# rev_1_3.net
KiCad netlist of a schematic drawn in EAGLE
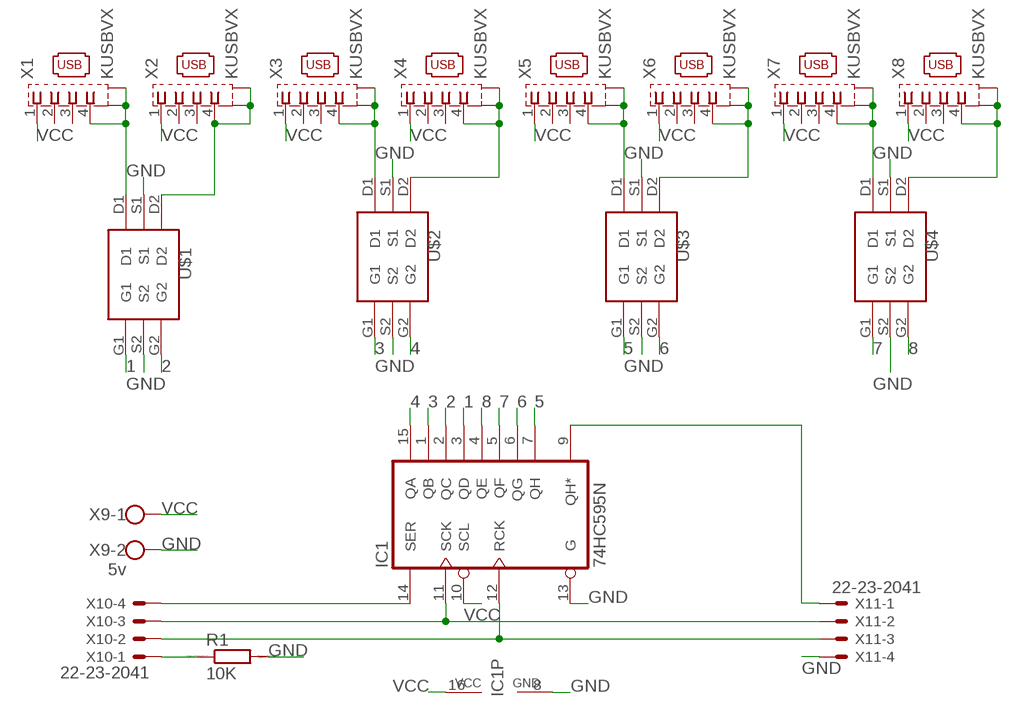
[diagram p0: schematic, sheet 1]

(export (version "E")
  (design (tool "Eeschema 10.0.6"))
  (components
    (comp (ref "IC1")
      (value "74HC595N")
      (footprint "eagle-import:DIL16")
      (libsource (lib "eagle-import") (part "74595NHC"))
    )
    (comp (ref "R1")
      (value "10K")
      (footprint "eagle-import:0204_7")
      (libsource (lib "eagle-import") (part "R0204/7"))
    )
    (comp (ref "U$1")
      (value "FDC6305N")
      (footprint "eagle-import:FDC6305")
      (libsource (lib "eagle-import") (part "FDC6305N"))
    )
    (comp (ref "U$2")
      (value "FDC6305N")
      (footprint "eagle-import:FDC6305")
      (libsource (lib "eagle-import") (part "FDC6305N"))
    )
    (comp (ref "U$3")
      (value "FDC6305N")
      (footprint "eagle-import:FDC6305")
      (libsource (lib "eagle-import") (part "FDC6305N"))
    )
    (comp (ref "U$4")
      (value "FDC6305N")
      (footprint "eagle-import:FDC6305")
      (libsource (lib "eagle-import") (part "FDC6305N"))
    )
    (comp (ref "X1")
      (value "KUSBVX")
      (footprint "eagle-import:KUSBVX")
      (libsource (lib "eagle-import") (part "KUSBVX"))
    )
    (comp (ref "X2")
      (value "KUSBVX")
      (footprint "eagle-import:KUSBVX")
      (libsource (lib "eagle-import") (part "KUSBVX"))
    )
    (comp (ref "X3")
      (value "KUSBVX")
      (footprint "eagle-import:KUSBVX")
      (libsource (lib "eagle-import") (part "KUSBVX"))
    )
    (comp (ref "X4")
      (value "KUSBVX")
      (footprint "eagle-import:KUSBVX")
      (libsource (lib "eagle-import") (part "KUSBVX"))
    )
    (comp (ref "X5")
      (value "KUSBVX")
      (footprint "eagle-import:KUSBVX")
      (libsource (lib "eagle-import") (part "KUSBVX"))
    )
    (comp (ref "X6")
      (value "KUSBVX")
      (footprint "eagle-import:KUSBVX")
      (libsource (lib "eagle-import") (part "KUSBVX"))
    )
    (comp (ref "X7")
      (value "KUSBVX")
      (footprint "eagle-import:KUSBVX")
      (libsource (lib "eagle-import") (part "KUSBVX"))
    )
    (comp (ref "X8")
      (value "KUSBVX")
      (footprint "eagle-import:KUSBVX")
      (libsource (lib "eagle-import") (part "KUSBVX"))
    )
    (comp (ref "X9")
      (value "5v")
      (footprint "eagle-import:W237-102")
      (fields (field (name "MPN") "237-102"))
      (libsource (lib "eagle-import") (part "W237-102"))
    )
    (comp (ref "X10")
      (value "22-23-2041")
      (footprint "eagle-import:22-23-2041")
      (fields (field (name "MF") "MOLEX"))
      (libsource (lib "eagle-import") (part "22-23-2041"))
    )
    (comp (ref "X11")
      (value "22-23-2041")
      (footprint "eagle-import:22-23-2041")
      (fields (field (name "MF") "MOLEX"))
      (libsource (lib "eagle-import") (part "22-23-2041"))
    )
  )
  (nets
    (net (code "1") (name "/1") (class "Default")
      (node (ref "IC1") (pin "3") (pinfunction "QD_3") (pintype "tri_state"))
      (node (ref "U$1") (pin "G1") (pinfunction "G1_G1") (pintype "bidirectional"))
    )
    (net (code "2") (name "/2") (class "Default")
      (node (ref "IC1") (pin "2") (pinfunction "QC_2") (pintype "tri_state"))
      (node (ref "U$1") (pin "G2") (pinfunction "G2_G2") (pintype "bidirectional"))
    )
    (net (code "3") (name "/3") (class "Default")
      (node (ref "IC1") (pin "1") (pinfunction "QB_1") (pintype "tri_state"))
      (node (ref "U$2") (pin "G1") (pinfunction "G1_G1") (pintype "bidirectional"))
    )
    (net (code "4") (name "/4") (class "Default")
      (node (ref "IC1") (pin "15") (pinfunction "QA_15") (pintype "tri_state"))
      (node (ref "U$2") (pin "G2") (pinfunction "G2_G2") (pintype "bidirectional"))
    )
    (net (code "5") (name "/5") (class "Default")
      (node (ref "IC1") (pin "7") (pinfunction "QH_7") (pintype "tri_state"))
      (node (ref "U$3") (pin "G1") (pinfunction "G1_G1") (pintype "bidirectional"))
    )
    (net (code "6") (name "/6") (class "Default")
      (node (ref "IC1") (pin "6") (pinfunction "QG_6") (pintype "tri_state"))
      (node (ref "U$3") (pin "G2") (pinfunction "G2_G2") (pintype "bidirectional"))
    )
    (net (code "7") (name "/7") (class "Default")
      (node (ref "IC1") (pin "5") (pinfunction "QF_5") (pintype "tri_state"))
      (node (ref "U$4") (pin "G1") (pinfunction "G1_G1") (pintype "bidirectional"))
    )
    (net (code "8") (name "/8") (class "Default")
      (node (ref "IC1") (pin "4") (pinfunction "QE_4") (pintype "tri_state"))
      (node (ref "U$4") (pin "G2") (pinfunction "G2_G2") (pintype "bidirectional"))
    )
    (net (code "9") (name "/GND") (class "Default")
      (node (ref "IC1") (pin "13") (pinfunction "G_13") (pintype "input"))
      (node (ref "IC1") (pin "8") (pinfunction "GND_8") (pintype "power_in"))
      (node (ref "R1") (pin "2") (pinfunction "2_2") (pintype "passive"))
      (node (ref "U$1") (pin "S1") (pinfunction "S1_S1") (pintype "bidirectional"))
      (node (ref "U$1") (pin "S2") (pinfunction "S2_S2") (pintype "bidirectional"))
      (node (ref "U$2") (pin "S1") (pinfunction "S1_S1") (pintype "bidirectional"))
      (node (ref "U$2") (pin "S2") (pinfunction "S2_S2") (pintype "bidirectional"))
      (node (ref "U$3") (pin "S1") (pinfunction "S1_S1") (pintype "bidirectional"))
      (node (ref "U$3") (pin "S2") (pinfunction "S2_S2") (pintype "bidirectional"))
      (node (ref "U$4") (pin "S1") (pinfunction "S1_S1") (pintype "bidirectional"))
      (node (ref "U$4") (pin "S2") (pinfunction "S2_S2") (pintype "bidirectional"))
      (node (ref "X11") (pin "4") (pinfunction "S_4") (pintype "passive"))
      (node (ref "X9") (pin "2") (pinfunction "KL_2") (pintype "passive"))
    )
    (net (code "10") (name "/VCC") (class "Default")
      (node (ref "IC1") (pin "10") (pinfunction "SCL_10") (pintype "input"))
      (node (ref "IC1") (pin "16") (pinfunction "VCC_16") (pintype "power_in"))
      (node (ref "X1") (pin "1") (pinfunction "1_1") (pintype "passive"))
      (node (ref "X2") (pin "1") (pinfunction "1_1") (pintype "passive"))
      (node (ref "X3") (pin "1") (pinfunction "1_1") (pintype "passive"))
      (node (ref "X4") (pin "1") (pinfunction "1_1") (pintype "passive"))
      (node (ref "X5") (pin "1") (pinfunction "1_1") (pintype "passive"))
      (node (ref "X6") (pin "1") (pinfunction "1_1") (pintype "passive"))
      (node (ref "X7") (pin "1") (pinfunction "1_1") (pintype "passive"))
      (node (ref "X8") (pin "1") (pinfunction "1_1") (pintype "passive"))
      (node (ref "X9") (pin "1") (pinfunction "KL_1") (pintype "passive"))
    )
    (net (code "11") (name "Net-(IC1A-QH*)") (class "Default")
      (node (ref "IC1") (pin "9") (pinfunction "QH*_9") (pintype "tri_state"))
      (node (ref "X11") (pin "1") (pinfunction "S_1") (pintype "passive"))
    )
    (net (code "12") (name "Net-(IC1A-RCK)") (class "Default")
      (node (ref "IC1") (pin "12") (pinfunction "RCK_12") (pintype "input"))
      (node (ref "X10") (pin "2") (pinfunction "S_2") (pintype "passive"))
      (node (ref "X11") (pin "3") (pinfunction "S_3") (pintype "passive"))
    )
    (net (code "13") (name "Net-(IC1A-SCK)") (class "Default")
      (node (ref "IC1") (pin "11") (pinfunction "SCK_11") (pintype "input"))
      (node (ref "X10") (pin "3") (pinfunction "S_3") (pintype "passive"))
      (node (ref "X11") (pin "2") (pinfunction "S_2") (pintype "passive"))
    )
    (net (code "14") (name "Net-(IC1A-SER)") (class "Default")
      (node (ref "IC1") (pin "14") (pinfunction "SER_14") (pintype "input"))
      (node (ref "X10") (pin "4") (pinfunction "S_4") (pintype "passive"))
    )
    (net (code "15") (name "Net-(X1-S1)") (class "Default")
      (node (ref "U$1") (pin "D1") (pinfunction "D1_D1") (pintype "bidirectional"))
      (node (ref "X1") (pin "4") (pinfunction "4_4") (pintype "passive"))
      (node (ref "X1") (pin "M1") (pinfunction "S1_M1") (pintype "passive"))
      (node (ref "X1") (pin "M2") (pinfunction "S2_M2") (pintype "passive"))
    )
    (net (code "16") (name "Net-(X2-S1)") (class "Default")
      (node (ref "U$1") (pin "D2") (pinfunction "D2_D2") (pintype "bidirectional"))
      (node (ref "X2") (pin "4") (pinfunction "4_4") (pintype "passive"))
      (node (ref "X2") (pin "M1") (pinfunction "S1_M1") (pintype "passive"))
      (node (ref "X2") (pin "M2") (pinfunction "S2_M2") (pintype "passive"))
    )
    (net (code "17") (name "Net-(X3-S1)") (class "Default")
      (node (ref "U$2") (pin "D1") (pinfunction "D1_D1") (pintype "bidirectional"))
      (node (ref "X3") (pin "4") (pinfunction "4_4") (pintype "passive"))
      (node (ref "X3") (pin "M1") (pinfunction "S1_M1") (pintype "passive"))
      (node (ref "X3") (pin "M2") (pinfunction "S2_M2") (pintype "passive"))
    )
    (net (code "18") (name "Net-(X4-S1)") (class "Default")
      (node (ref "U$2") (pin "D2") (pinfunction "D2_D2") (pintype "bidirectional"))
      (node (ref "X4") (pin "4") (pinfunction "4_4") (pintype "passive"))
      (node (ref "X4") (pin "M1") (pinfunction "S1_M1") (pintype "passive"))
      (node (ref "X4") (pin "M2") (pinfunction "S2_M2") (pintype "passive"))
    )
    (net (code "19") (name "Net-(X5-S1)") (class "Default")
      (node (ref "U$3") (pin "D1") (pinfunction "D1_D1") (pintype "bidirectional"))
      (node (ref "X5") (pin "4") (pinfunction "4_4") (pintype "passive"))
      (node (ref "X5") (pin "M1") (pinfunction "S1_M1") (pintype "passive"))
      (node (ref "X5") (pin "M2") (pinfunction "S2_M2") (pintype "passive"))
    )
    (net (code "20") (name "Net-(X6-S1)") (class "Default")
      (node (ref "U$3") (pin "D2") (pinfunction "D2_D2") (pintype "bidirectional"))
      (node (ref "X6") (pin "4") (pinfunction "4_4") (pintype "passive"))
      (node (ref "X6") (pin "M1") (pinfunction "S1_M1") (pintype "passive"))
      (node (ref "X6") (pin "M2") (pinfunction "S2_M2") (pintype "passive"))
    )
    (net (code "21") (name "Net-(X7-S1)") (class "Default")
      (node (ref "U$4") (pin "D1") (pinfunction "D1_D1") (pintype "bidirectional"))
      (node (ref "X7") (pin "4") (pinfunction "4_4") (pintype "passive"))
      (node (ref "X7") (pin "M1") (pinfunction "S1_M1") (pintype "passive"))
      (node (ref "X7") (pin "M2") (pinfunction "S2_M2") (pintype "passive"))
    )
    (net (code "22") (name "Net-(X8-S1)") (class "Default")
      (node (ref "U$4") (pin "D2") (pinfunction "D2_D2") (pintype "bidirectional"))
      (node (ref "X8") (pin "4") (pinfunction "4_4") (pintype "passive"))
      (node (ref "X8") (pin "M1") (pinfunction "S1_M1") (pintype "passive"))
      (node (ref "X8") (pin "M2") (pinfunction "S2_M2") (pintype "passive"))
    )
    (net (code "23") (name "Net-(X10A-S)") (class "Default")
      (node (ref "R1") (pin "1") (pinfunction "1_1") (pintype "passive"))
      (node (ref "X10") (pin "1") (pinfunction "S_1") (pintype "passive"))
    )
    (net (code "24") (name "unconnected-(X1-Pad2)") (class "Default")
      (node (ref "X1") (pin "2") (pinfunction "2_2") (pintype "passive"))
    )
    (net (code "25") (name "unconnected-(X1-Pad3)") (class "Default")
      (node (ref "X1") (pin "3") (pinfunction "3_3") (pintype "passive"))
    )
    (net (code "26") (name "unconnected-(X2-Pad2)") (class "Default")
      (node (ref "X2") (pin "2") (pinfunction "2_2") (pintype "passive"))
    )
    (net (code "27") (name "unconnected-(X2-Pad3)") (class "Default")
      (node (ref "X2") (pin "3") (pinfunction "3_3") (pintype "passive"))
    )
    (net (code "28") (name "unconnected-(X3-Pad2)") (class "Default")
      (node (ref "X3") (pin "2") (pinfunction "2_2") (pintype "passive"))
    )
    (net (code "29") (name "unconnected-(X3-Pad3)") (class "Default")
      (node (ref "X3") (pin "3") (pinfunction "3_3") (pintype "passive"))
    )
    (net (code "30") (name "unconnected-(X4-Pad2)") (class "Default")
      (node (ref "X4") (pin "2") (pinfunction "2_2") (pintype "passive"))
    )
    (net (code "31") (name "unconnected-(X4-Pad3)") (class "Default")
      (node (ref "X4") (pin "3") (pinfunction "3_3") (pintype "passive"))
    )
    (net (code "32") (name "unconnected-(X5-Pad2)") (class "Default")
      (node (ref "X5") (pin "2") (pinfunction "2_2") (pintype "passive"))
    )
    (net (code "33") (name "unconnected-(X5-Pad3)") (class "Default")
      (node (ref "X5") (pin "3") (pinfunction "3_3") (pintype "passive"))
    )
    (net (code "34") (name "unconnected-(X6-Pad2)") (class "Default")
      (node (ref "X6") (pin "2") (pinfunction "2_2") (pintype "passive"))
    )
    (net (code "35") (name "unconnected-(X6-Pad3)") (class "Default")
      (node (ref "X6") (pin "3") (pinfunction "3_3") (pintype "passive"))
    )
    (net (code "36") (name "unconnected-(X7-Pad2)") (class "Default")
      (node (ref "X7") (pin "2") (pinfunction "2_2") (pintype "passive"))
    )
    (net (code "37") (name "unconnected-(X7-Pad3)") (class "Default")
      (node (ref "X7") (pin "3") (pinfunction "3_3") (pintype "passive"))
    )
    (net (code "38") (name "unconnected-(X8-Pad2)") (class "Default")
      (node (ref "X8") (pin "2") (pinfunction "2_2") (pintype "passive"))
    )
    (net (code "39") (name "unconnected-(X8-Pad3)") (class "Default")
      (node (ref "X8") (pin "3") (pinfunction "3_3") (pintype "passive"))
    )
  )
)
